# max232.net
KiCad netlist of a schematic drawn in EAGLE
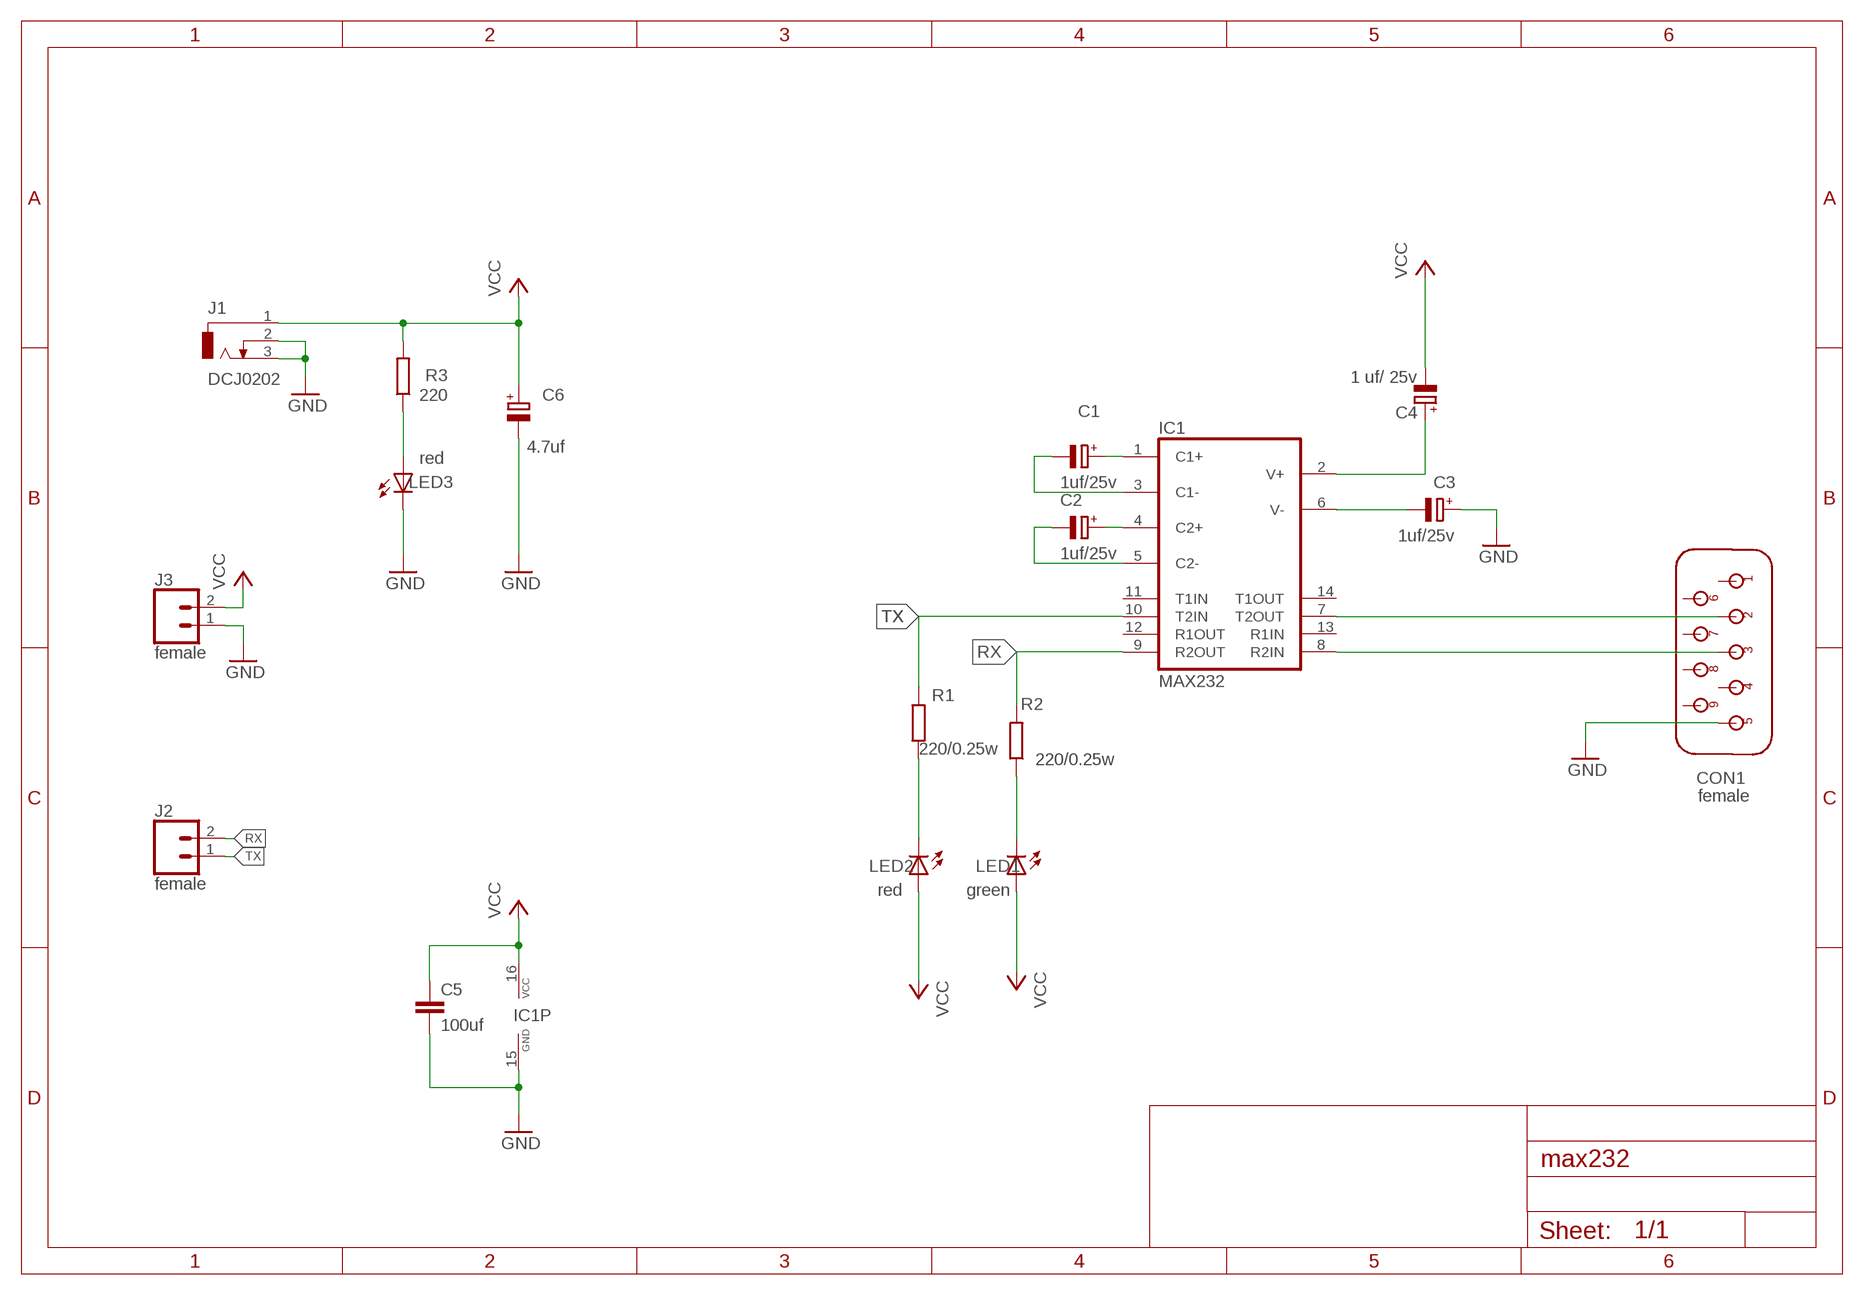
[diagram p0: schematic, sheet 1]

(export (version "E")
  (design (tool "Eeschema 10.0.6"))
  (components
    (comp (ref "C1")
      (value "1uf/25v")
      (footprint "eagle-import:E2,5-6")
      (libsource (lib "eagle-import") (part "CPOL-EUE2.5-6"))
    )
    (comp (ref "C2")
      (value "1uf/25v")
      (footprint "eagle-import:E2,5-6")
      (libsource (lib "eagle-import") (part "CPOL-EUE2.5-6"))
    )
    (comp (ref "C3")
      (value "1uf/25v")
      (footprint "eagle-import:E2,5-6")
      (libsource (lib "eagle-import") (part "CPOL-EUE2.5-6"))
    )
    (comp (ref "C4")
      (value "1 uf/ 25v")
      (footprint "eagle-import:E2,5-6")
      (libsource (lib "eagle-import") (part "CPOL-EUE2.5-6"))
    )
    (comp (ref "C5")
      (value "100uf")
      (footprint "eagle-import:C025-024X044")
      (libsource (lib "eagle-import") (part "C-EU025-024X044"))
    )
    (comp (ref "C6")
      (value "4.7uf")
      (footprint "eagle-import:E2,5-6")
      (libsource (lib "eagle-import") (part "CPOL-EUE2.5-6"))
    )
    (comp (ref "CON1")
      (value "female")
      (footprint "eagle-import:D-09F_90")
      (libsource (lib "eagle-import") (part "DB9F/90"))
    )
    (comp (ref "IC1")
      (value "MAX232")
      (footprint "eagle-import:DIL16")
      (fields (field (name "MF") "MAXIM") (field (name "MPN") "MAX232ACPE+"))
      (libsource (lib "eagle-import") (part "MAX232"))
    )
    (comp (ref "J1")
      (value "DCJ0202")
      (footprint "eagle-import:DCJ0202")
      (libsource (lib "eagle-import") (part "DCJ0202"))
    )
    (comp (ref "J2")
      (value "female")
      (footprint "eagle-import:1X02")
      (libsource (lib "eagle-import") (part "CONN_02"))
    )
    (comp (ref "J3")
      (value "female")
      (footprint "eagle-import:1X02")
      (libsource (lib "eagle-import") (part "CONN_02"))
    )
    (comp (ref "LED1")
      (value "green")
      (footprint "eagle-import:LED3MM")
      (libsource (lib "eagle-import") (part "LED3MM"))
    )
    (comp (ref "LED2")
      (value "red")
      (footprint "eagle-import:LED3MM")
      (libsource (lib "eagle-import") (part "LED3MM"))
    )
    (comp (ref "LED3")
      (value "red")
      (footprint "eagle-import:LED3MM")
      (libsource (lib "eagle-import") (part "LED3MM"))
    )
    (comp (ref "R1")
      (value "220/0.25w")
      (footprint "eagle-import:0207_10")
      (libsource (lib "eagle-import") (part "R-EU_0207/10"))
    )
    (comp (ref "R2")
      (value "220/0.25w")
      (footprint "eagle-import:0207_10")
      (libsource (lib "eagle-import") (part "R-EU_0207/10"))
    )
    (comp (ref "R3")
      (value "220")
      (footprint "eagle-import:0207_10")
      (libsource (lib "eagle-import") (part "R-EU_0207/10"))
    )
  )
  (nets
    (net (code "1") (name "GND") (class "Default")
      (node (ref "C3") (pin "+") (pinfunction "+_+") (pintype "passive"))
      (node (ref "C5") (pin "2") (pinfunction "2_2") (pintype "passive"))
      (node (ref "C6") (pin "-") (pinfunction "-_-") (pintype "passive"))
      (node (ref "CON1") (pin "5") (pinfunction "5_5") (pintype "passive"))
      (node (ref "IC1") (pin "15") (pinfunction "GND_15") (pintype "power_in"))
      (node (ref "J1") (pin "2") (pinfunction "2_2") (pintype "passive"))
      (node (ref "J1") (pin "3") (pinfunction "3_3") (pintype "passive"))
      (node (ref "J3") (pin "1") (pinfunction "1_1") (pintype "passive"))
      (node (ref "LED3") (pin "K") (pinfunction "C_K") (pintype "passive"))
    )
    (net (code "2") (name "Net-(IC1A-C1+)") (class "Default")
      (node (ref "C1") (pin "+") (pinfunction "+_+") (pintype "passive"))
      (node (ref "IC1") (pin "1") (pinfunction "C1+_1") (pintype "bidirectional"))
    )
    (net (code "3") (name "Net-(IC1A-C1-)") (class "Default")
      (node (ref "C1") (pin "-") (pinfunction "-_-") (pintype "passive"))
      (node (ref "IC1") (pin "3") (pinfunction "C1-_3") (pintype "bidirectional"))
    )
    (net (code "4") (name "Net-(IC1A-C2+)") (class "Default")
      (node (ref "C2") (pin "+") (pinfunction "+_+") (pintype "passive"))
      (node (ref "IC1") (pin "4") (pinfunction "C2+_4") (pintype "bidirectional"))
    )
    (net (code "5") (name "Net-(IC1A-C2-)") (class "Default")
      (node (ref "C2") (pin "-") (pinfunction "-_-") (pintype "passive"))
      (node (ref "IC1") (pin "5") (pinfunction "C2-_5") (pintype "bidirectional"))
    )
    (net (code "6") (name "Net-(IC1A-R2IN)") (class "Default")
      (node (ref "CON1") (pin "3") (pinfunction "3_3") (pintype "passive"))
      (node (ref "IC1") (pin "8") (pinfunction "R2IN_8") (pintype "input"))
    )
    (net (code "7") (name "Net-(IC1A-T2OUT)") (class "Default")
      (node (ref "CON1") (pin "2") (pinfunction "2_2") (pintype "passive"))
      (node (ref "IC1") (pin "7") (pinfunction "T2OUT_7") (pintype "output"))
    )
    (net (code "8") (name "Net-(IC1A-V+)") (class "Default")
      (node (ref "C4") (pin "+") (pinfunction "+_+") (pintype "passive"))
      (node (ref "IC1") (pin "2") (pinfunction "V+_2") (pintype "bidirectional"))
    )
    (net (code "9") (name "Net-(IC1A-V-)") (class "Default")
      (node (ref "C3") (pin "-") (pinfunction "-_-") (pintype "passive"))
      (node (ref "IC1") (pin "6") (pinfunction "V-_6") (pintype "bidirectional"))
    )
    (net (code "10") (name "Net-(LED1-C)") (class "Default")
      (node (ref "LED1") (pin "K") (pinfunction "C_K") (pintype "passive"))
      (node (ref "R2") (pin "1") (pinfunction "1_1") (pintype "passive"))
    )
    (net (code "11") (name "Net-(LED2-C)") (class "Default")
      (node (ref "LED2") (pin "K") (pinfunction "C_K") (pintype "passive"))
      (node (ref "R1") (pin "1") (pinfunction "1_1") (pintype "passive"))
    )
    (net (code "12") (name "Net-(LED3-PadA)") (class "Default")
      (node (ref "LED3") (pin "A") (pinfunction "A_A") (pintype "passive"))
      (node (ref "R3") (pin "1") (pinfunction "1_1") (pintype "passive"))
    )
    (net (code "13") (name "RX") (class "Default")
      (node (ref "IC1") (pin "9") (pinfunction "R2OUT_9") (pintype "output"))
      (node (ref "J2") (pin "2") (pinfunction "2_2") (pintype "passive"))
      (node (ref "R2") (pin "2") (pinfunction "2_2") (pintype "passive"))
    )
    (net (code "14") (name "TX") (class "Default")
      (node (ref "IC1") (pin "10") (pinfunction "T2IN_10") (pintype "input"))
      (node (ref "J2") (pin "1") (pinfunction "1_1") (pintype "passive"))
      (node (ref "R1") (pin "2") (pinfunction "2_2") (pintype "passive"))
    )
    (net (code "15") (name "VCC") (class "Default")
      (node (ref "C4") (pin "-") (pinfunction "-_-") (pintype "passive"))
      (node (ref "C5") (pin "1") (pinfunction "1_1") (pintype "passive"))
      (node (ref "C6") (pin "+") (pinfunction "+_+") (pintype "passive"))
      (node (ref "IC1") (pin "16") (pinfunction "VCC_16") (pintype "power_in"))
      (node (ref "J1") (pin "1") (pinfunction "1_1") (pintype "passive"))
      (node (ref "J3") (pin "2") (pinfunction "2_2") (pintype "passive"))
      (node (ref "LED1") (pin "A") (pinfunction "A_A") (pintype "passive"))
      (node (ref "LED2") (pin "A") (pinfunction "A_A") (pintype "passive"))
      (node (ref "R3") (pin "2") (pinfunction "2_2") (pintype "passive"))
    )
    (net (code "16") (name "unconnected-(CON1-Pad1)") (class "Default")
      (node (ref "CON1") (pin "1") (pinfunction "1_1") (pintype "passive"))
    )
    (net (code "17") (name "unconnected-(CON1-Pad4)") (class "Default")
      (node (ref "CON1") (pin "4") (pinfunction "4_4") (pintype "passive"))
    )
    (net (code "18") (name "unconnected-(CON1-Pad6)") (class "Default")
      (node (ref "CON1") (pin "6") (pinfunction "6_6") (pintype "passive"))
    )
    (net (code "19") (name "unconnected-(CON1-Pad7)") (class "Default")
      (node (ref "CON1") (pin "7") (pinfunction "7_7") (pintype "passive"))
    )
    (net (code "20") (name "unconnected-(CON1-Pad8)") (class "Default")
      (node (ref "CON1") (pin "8") (pinfunction "8_8") (pintype "passive"))
    )
    (net (code "21") (name "unconnected-(CON1-Pad9)") (class "Default")
      (node (ref "CON1") (pin "9") (pinfunction "9_9") (pintype "passive"))
    )
    (net (code "22") (name "unconnected-(IC1A-R1IN-Pad13)") (class "Default")
      (node (ref "IC1") (pin "13") (pinfunction "R1IN_13") (pintype "input"))
    )
    (net (code "23") (name "unconnected-(IC1A-R1OUT-Pad12)") (class "Default")
      (node (ref "IC1") (pin "12") (pinfunction "R1OUT_12") (pintype "output"))
    )
    (net (code "24") (name "unconnected-(IC1A-T1IN-Pad11)") (class "Default")
      (node (ref "IC1") (pin "11") (pinfunction "T1IN_11") (pintype "input"))
    )
    (net (code "25") (name "unconnected-(IC1A-T1OUT-Pad14)") (class "Default")
      (node (ref "IC1") (pin "14") (pinfunction "T1OUT_14") (pintype "output"))
    )
  )
)
